# main.net
KiCad netlist of a schematic drawn in Altium Designer
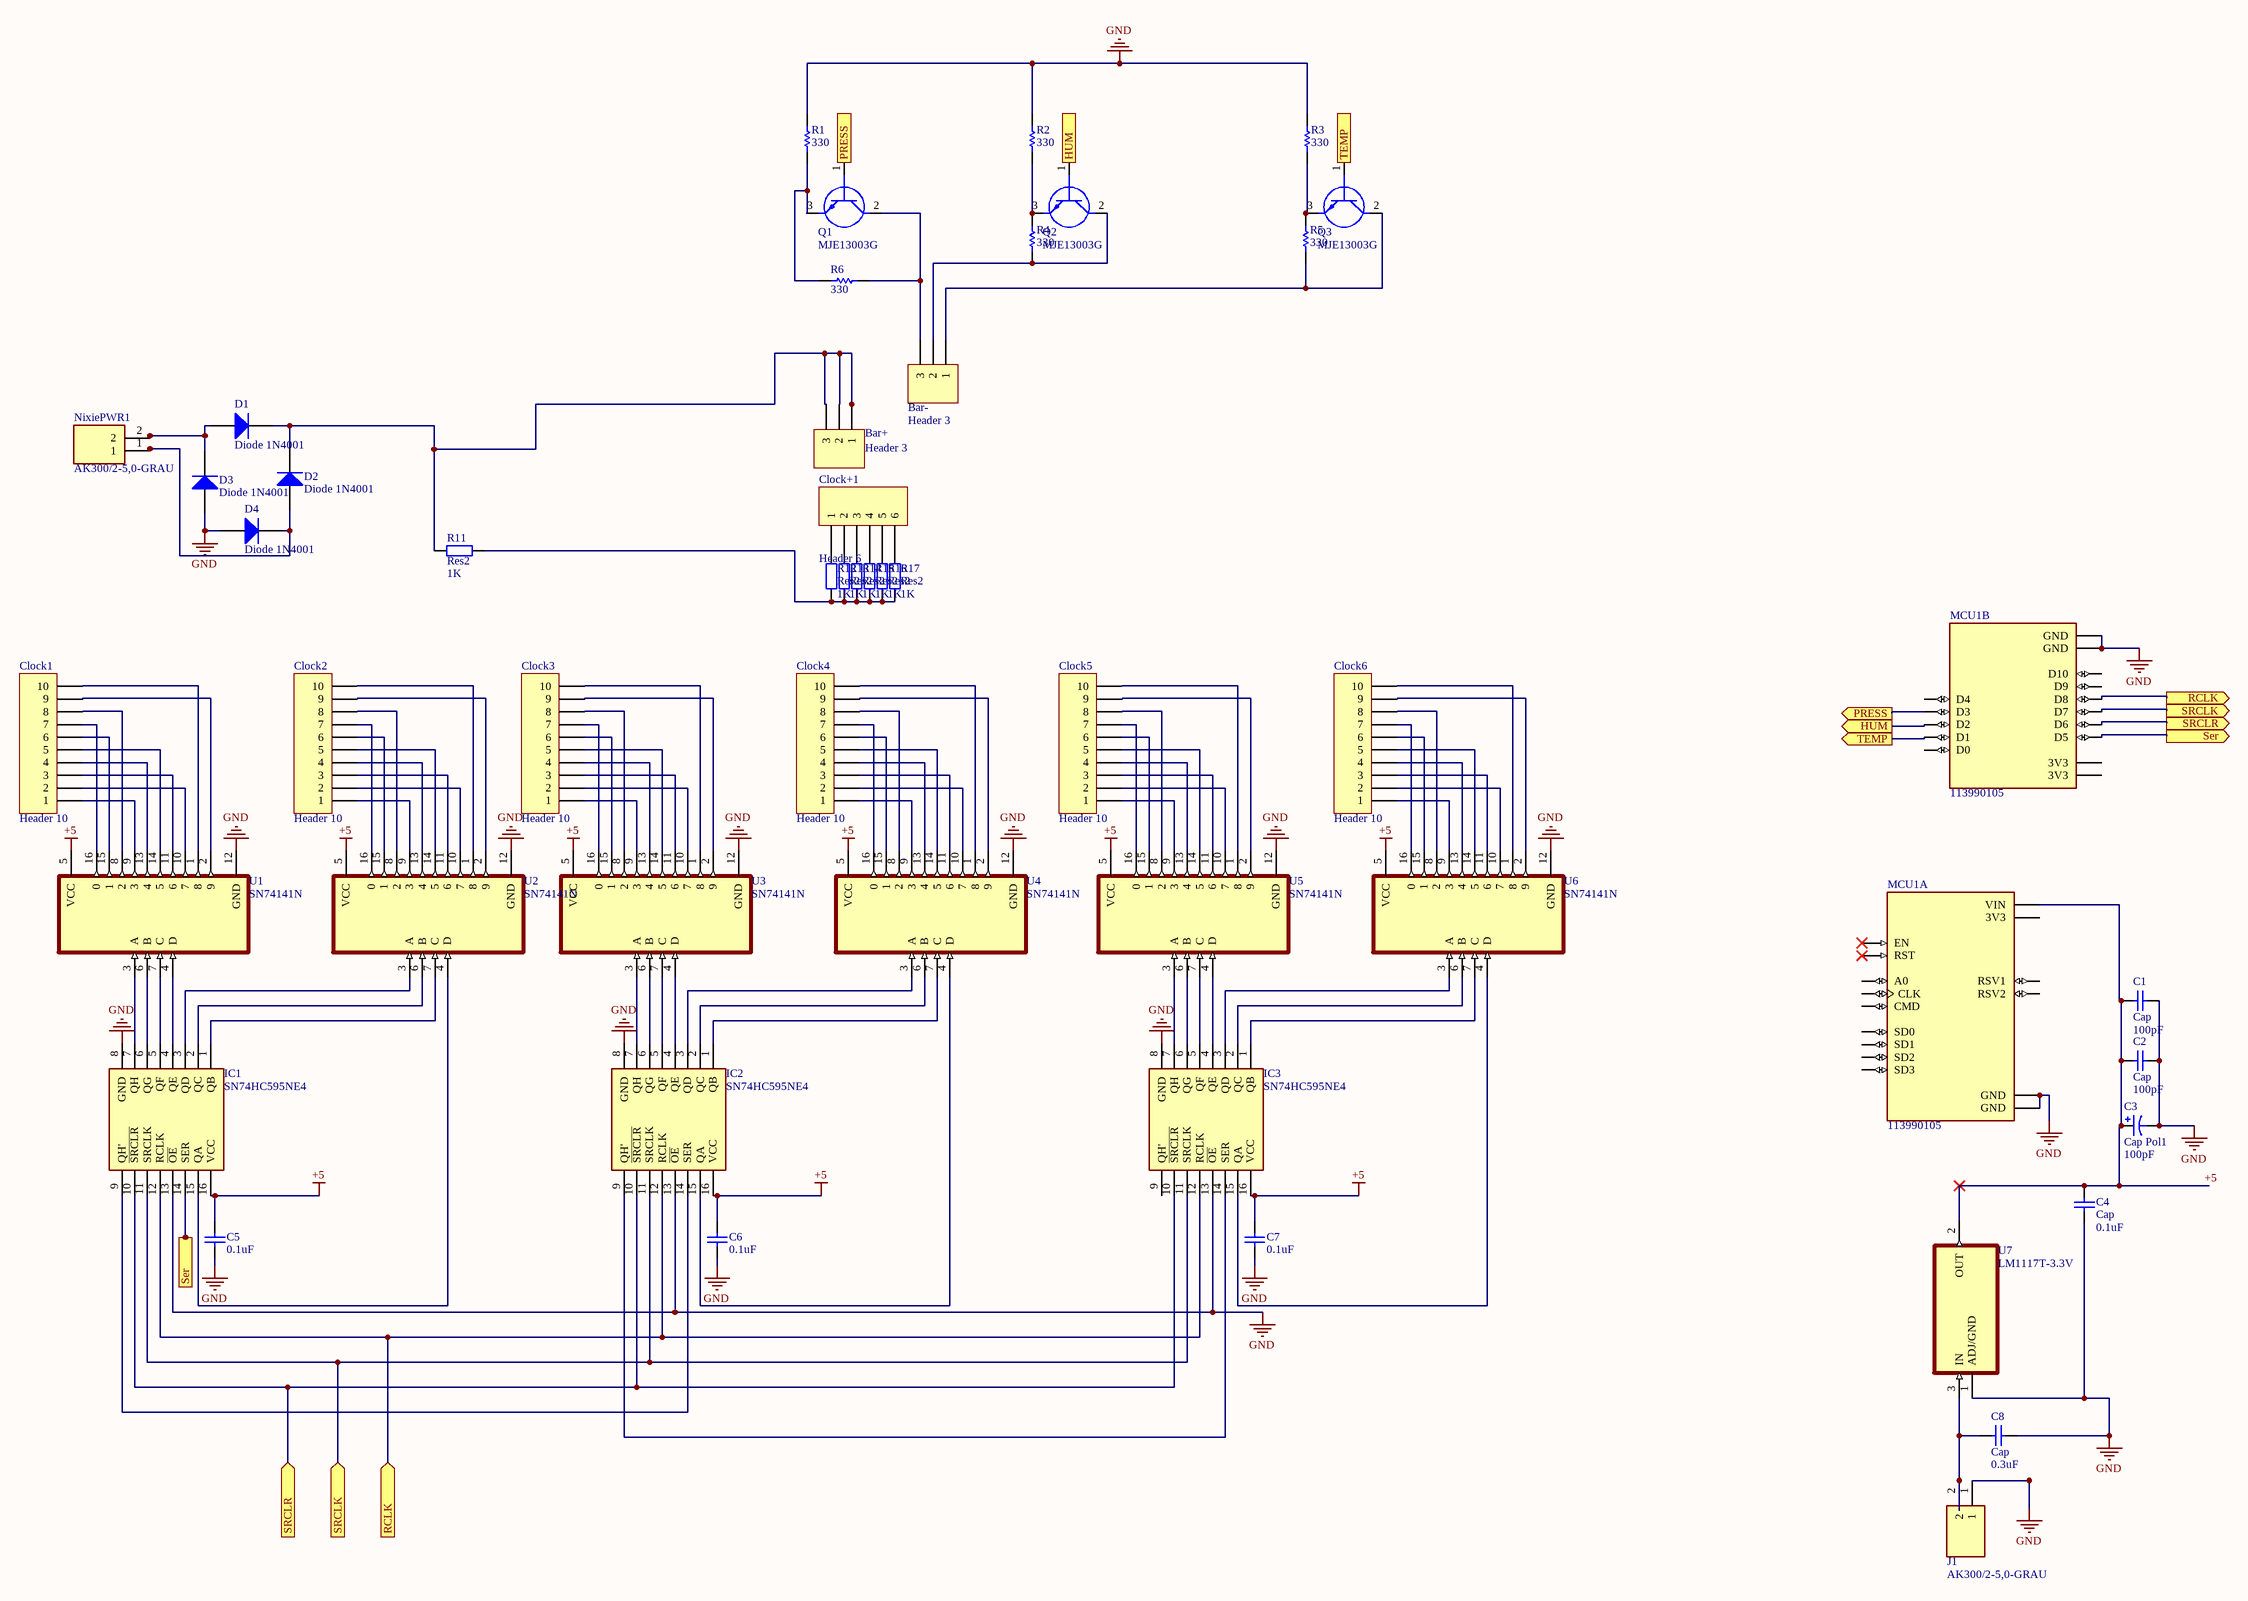
[diagram p0: main.SchDoc]

(export (version "E")
  (design (tool "Eeschema 10.0.6"))
  (components
    (comp (ref "Bar+")
      (value "Header 3")
      (footprint "HDR1X3")
      (description "Header, 3-Pin")
      (fields (field (name "PUBLISHER") "Altium Limited"))
      (libsource (lib "Miscellaneous Connectors") (part "Header 3"))
    )
    (comp (ref "Bar-")
      (value "Header 3")
      (footprint "HDR1X3")
      (description "Header, 3-Pin")
      (fields (field (name "PUBLISHER") "Altium Limited"))
      (libsource (lib "Miscellaneous Connectors") (part "Header 3"))
    )
    (comp (ref "C1")
      (value "Cap")
      (footprint "AXIAL-0.3")
      (description "Capacitor")
      (fields (field (name "ALTIUM_VALUE") "100pF") (field (name "PUBLISHER") "Altium Limited"))
      (libsource (lib "Miscellaneous Devices") (part "Cap"))
    )
    (comp (ref "C2")
      (value "Cap")
      (footprint "AXIAL-0.3")
      (description "Capacitor")
      (fields (field (name "ALTIUM_VALUE") "100pF") (field (name "PUBLISHER") "Altium Limited"))
      (libsource (lib "Miscellaneous Devices") (part "Cap"))
    )
    (comp (ref "C3")
      (value "Cap Pol1")
      (footprint "CAPR5-4X5")
      (description "Polarized Capacitor (Radial)")
      (fields (field (name "ALTIUM_VALUE") "100pF") (field (name "PUBLISHER") "Altium Limited"))
      (libsource (lib "Miscellaneous Devices") (part "Cap Pol1"))
    )
    (comp (ref "C4")
      (value "Cap")
      (footprint "AXIAL-0.3")
      (description "Capacitor")
      (fields (field (name "ALTIUM_VALUE") "0.1uF") (field (name "PUBLISHER") "Altium Limited"))
      (libsource (lib "Miscellaneous Devices") (part "Cap"))
    )
    (comp (ref "C5")
      (value "0.1uF")
      (footprint "AXIAL-0.3")
      (description "Capacitor")
      (fields (field (name "Comment") "Cap") (field (name "PUBLISHER") "Altium Limited"))
      (libsource (lib "Miscellaneous Devices") (part "Cap"))
    )
    (comp (ref "C6")
      (value "0.1uF")
      (footprint "AXIAL-0.3")
      (description "Capacitor")
      (fields (field (name "Comment") "Cap") (field (name "PUBLISHER") "Altium Limited"))
      (libsource (lib "Miscellaneous Devices") (part "Cap"))
    )
    (comp (ref "C7")
      (value "0.1uF")
      (footprint "AXIAL-0.3")
      (description "Capacitor")
      (fields (field (name "Comment") "Cap") (field (name "PUBLISHER") "Altium Limited"))
      (libsource (lib "Miscellaneous Devices") (part "Cap"))
    )
    (comp (ref "C8")
      (value "Cap")
      (footprint "AXIAL-0.3")
      (description "Capacitor")
      (fields (field (name "ALTIUM_VALUE") "0.3uF") (field (name "PUBLISHER") "Altium Limited"))
      (libsource (lib "Miscellaneous Devices") (part "Cap"))
    )
    (comp (ref "Clock+1")
      (value "Header 6")
      (footprint "HDR1X6")
      (description "Header, 6-Pin")
      (fields (field (name "PUBLISHER") "Altium Limited"))
      (libsource (lib "Miscellaneous Connectors") (part "Header 6"))
    )
    (comp (ref "Clock1")
      (value "Header 10")
      (footprint "HDR1X10")
      (description "Header, 10-Pin")
      (fields (field (name "PUBLISHER") "Altium Limited"))
      (libsource (lib "Miscellaneous Connectors") (part "Header 10"))
    )
    (comp (ref "Clock2")
      (value "Header 10")
      (footprint "HDR1X10")
      (description "Header, 10-Pin")
      (fields (field (name "PUBLISHER") "Altium Limited"))
      (libsource (lib "Miscellaneous Connectors") (part "Header 10"))
    )
    (comp (ref "Clock3")
      (value "Header 10")
      (footprint "HDR1X10")
      (description "Header, 10-Pin")
      (fields (field (name "PUBLISHER") "Altium Limited"))
      (libsource (lib "Miscellaneous Connectors") (part "Header 10"))
    )
    (comp (ref "Clock4")
      (value "Header 10")
      (footprint "HDR1X10")
      (description "Header, 10-Pin")
      (fields (field (name "PUBLISHER") "Altium Limited"))
      (libsource (lib "Miscellaneous Connectors") (part "Header 10"))
    )
    (comp (ref "Clock5")
      (value "Header 10")
      (footprint "HDR1X10")
      (description "Header, 10-Pin")
      (fields (field (name "PUBLISHER") "Altium Limited"))
      (libsource (lib "Miscellaneous Connectors") (part "Header 10"))
    )
    (comp (ref "Clock6")
      (value "Header 10")
      (footprint "HDR1X10")
      (description "Header, 10-Pin")
      (fields (field (name "PUBLISHER") "Altium Limited"))
      (libsource (lib "Miscellaneous Connectors") (part "Header 10"))
    )
    (comp (ref "D1")
      (value "Diode 1N4001")
      (footprint "DO-41")
      (description "1 Amp General Purpose Rectifier")
      (fields (field (name "PUBLISHER") "Altium Limited"))
      (libsource (lib "Miscellaneous Devices") (part "Diode 1N4001"))
    )
    (comp (ref "D2")
      (value "Diode 1N4001")
      (footprint "DO-41")
      (description "1 Amp General Purpose Rectifier")
      (fields (field (name "PUBLISHER") "Altium Limited"))
      (libsource (lib "Miscellaneous Devices") (part "Diode 1N4001"))
    )
    (comp (ref "D3")
      (value "Diode 1N4001")
      (footprint "DO-41")
      (description "1 Amp General Purpose Rectifier")
      (fields (field (name "PUBLISHER") "Altium Limited"))
      (libsource (lib "Miscellaneous Devices") (part "Diode 1N4001"))
    )
    (comp (ref "D4")
      (value "Diode 1N4001")
      (footprint "DO-41")
      (description "1 Amp General Purpose Rectifier")
      (fields (field (name "PUBLISHER") "Altium Limited"))
      (libsource (lib "Miscellaneous Devices") (part "Diode 1N4001"))
    )
    (comp (ref "IC1")
      (value "SN74HC595NE4")
      (footprint "SamacSys:DIP794W53P254L1930H508Q16N")
      (description "Integrated Circuit")
      (fields (field (name "MOUSER PART NUMBER") "595-SN74HC595NE4"))
      (libsource (lib "*") (part "SN74HC595NE4"))
    )
    (comp (ref "IC2")
      (value "SN74HC595NE4")
      (footprint "SamacSys:DIP794W53P254L1930H508Q16N")
      (description "Integrated Circuit")
      (fields (field (name "MOUSER PART NUMBER") "595-SN74HC595NE4"))
      (libsource (lib "*") (part "SN74HC595NE4"))
    )
    (comp (ref "IC3")
      (value "SN74HC595NE4")
      (footprint "SamacSys:DIP794W53P254L1930H508Q16N")
      (description "Integrated Circuit")
      (fields (field (name "MOUSER PART NUMBER") "595-SN74HC595NE4"))
      (libsource (lib "*") (part "SN74HC595NE4"))
    )
    (comp (ref "J1")
      (value "AK300/2-5,0-GRAU")
      (footprint "*PTR_AK300/2-5,0-GRAU")
      (description "Terminal block; 5mm; angled 45Â°; ways: 2")
      (fields (field (name "MF") "PTR Messtechnik"))
      (libsource (lib "") (part "AK300/2-5,0-GRAU_1"))
    )
    (comp (ref "MCU1")
      (value "113990105")
      (footprint "*SEEED_113990105_113990105(Primary)")
      (fields (field (name "MP") "NodeMCU v2") (field (name "MF") "Seeed Technology"))
      (libsource (lib "") (part "113990105_1"))
    )
    (comp (ref "NixiePWR1")
      (value "AK300/2-5,0-GRAU")
      (footprint "*PTR_AK300/2-5,0-GRAU")
      (description "Terminal block; 5mm; angled 45Â°; ways: 2")
      (fields (field (name "MF") "PTR Messtechnik"))
      (libsource (lib "AK300_2-5_0-GRAU") (part "AK300/2-5,0-GRAU"))
    )
    (comp (ref "Q1")
      (value "MJE13003G")
      (footprint "SamacSys:TO229P300X760X1364-3P")
      (description "Transistor BJT NPN")
      (fields (field (name "MOUSER PART NUMBER") "863-MJE13003G"))
      (libsource (lib "*") (part "MJE13003G"))
    )
    (comp (ref "Q2")
      (value "MJE13003G")
      (footprint "SamacSys:TO229P300X760X1364-3P")
      (description "Transistor BJT NPN")
      (fields (field (name "MOUSER PART NUMBER") "863-MJE13003G"))
      (libsource (lib "*") (part "MJE13003G"))
    )
    (comp (ref "Q3")
      (value "MJE13003G")
      (footprint "SamacSys:TO229P300X760X1364-3P")
      (description "Transistor BJT NPN")
      (fields (field (name "MOUSER PART NUMBER") "863-MJE13003G"))
      (libsource (lib "*") (part "MJE13003G"))
    )
    (comp (ref "R1")
      (value "330")
      (footprint "AXIAL-0.3")
      (description "Resistor")
      (fields (field (name "PUBLISHER") "Altium Limited"))
      (libsource (lib "Miscellaneous Devices") (part "Res1"))
    )
    (comp (ref "R2")
      (value "330")
      (footprint "AXIAL-0.3")
      (description "Resistor")
      (fields (field (name "PUBLISHER") "Altium Limited"))
      (libsource (lib "Miscellaneous Devices") (part "Res1"))
    )
    (comp (ref "R3")
      (value "330")
      (footprint "AXIAL-0.3")
      (description "Resistor")
      (fields (field (name "PUBLISHER") "Altium Limited"))
      (libsource (lib "Miscellaneous Devices") (part "Res1"))
    )
    (comp (ref "R4")
      (value "330")
      (footprint "AXIAL-0.3")
      (description "Resistor")
      (fields (field (name "PUBLISHER") "Altium Limited"))
      (libsource (lib "Miscellaneous Devices") (part "Res1"))
    )
    (comp (ref "R5")
      (value "330")
      (footprint "AXIAL-0.3")
      (description "Resistor")
      (fields (field (name "PUBLISHER") "Altium Limited"))
      (libsource (lib "Miscellaneous Devices") (part "Res1"))
    )
    (comp (ref "R6")
      (value "330")
      (footprint "AXIAL-0.3")
      (description "Resistor")
      (fields (field (name "PUBLISHER") "Altium Limited"))
      (libsource (lib "Miscellaneous Devices") (part "Res1"))
    )
    (comp (ref "R11")
      (value "Res2")
      (footprint "AXIAL-0.4")
      (description "Resistor")
      (fields (field (name "ALTIUM_VALUE") "1K") (field (name "PUBLISHER") "Altium Limited"))
      (libsource (lib "") (part "Res2_1"))
    )
    (comp (ref "R12")
      (value "Res2")
      (footprint "AXIAL-0.4")
      (description "Resistor")
      (fields (field (name "ALTIUM_VALUE") "1K") (field (name "PUBLISHER") "Altium Limited"))
      (libsource (lib "Miscellaneous Devices") (part "Res2"))
    )
    (comp (ref "R13")
      (value "Res2")
      (footprint "AXIAL-0.4")
      (description "Resistor")
      (fields (field (name "ALTIUM_VALUE") "1K") (field (name "PUBLISHER") "Altium Limited"))
      (libsource (lib "Miscellaneous Devices") (part "Res2"))
    )
    (comp (ref "R14")
      (value "Res2")
      (footprint "AXIAL-0.4")
      (description "Resistor")
      (fields (field (name "ALTIUM_VALUE") "1K") (field (name "PUBLISHER") "Altium Limited"))
      (libsource (lib "Miscellaneous Devices") (part "Res2"))
    )
    (comp (ref "R15")
      (value "Res2")
      (footprint "AXIAL-0.4")
      (description "Resistor")
      (fields (field (name "ALTIUM_VALUE") "1K") (field (name "PUBLISHER") "Altium Limited"))
      (libsource (lib "Miscellaneous Devices") (part "Res2"))
    )
    (comp (ref "R16")
      (value "Res2")
      (footprint "AXIAL-0.4")
      (description "Resistor")
      (fields (field (name "ALTIUM_VALUE") "1K") (field (name "PUBLISHER") "Altium Limited"))
      (libsource (lib "Miscellaneous Devices") (part "Res2"))
    )
    (comp (ref "R17")
      (value "Res2")
      (footprint "AXIAL-0.4")
      (description "Resistor")
      (fields (field (name "ALTIUM_VALUE") "1K") (field (name "PUBLISHER") "Altium Limited"))
      (libsource (lib "Miscellaneous Devices") (part "Res2"))
    )
    (comp (ref "U1")
      (value "SN74141N")
      (footprint "*DIP762W46P254L2134H508Q16")
      (description "BCD to DECIMAL Decoder/Driver")
      (fields (field (name "MF") "Texas Instruments"))
      (libsource (lib "SN74141N") (part "SN74141N"))
    )
    (comp (ref "U2")
      (value "SN74141N")
      (footprint "*DIP762W46P254L2134H508Q16")
      (description "BCD to DECIMAL Decoder/Driver")
      (fields (field (name "MF") "Texas Instruments"))
      (libsource (lib "SN74141N") (part "SN74141N"))
    )
    (comp (ref "U3")
      (value "SN74141N")
      (footprint "*DIP762W46P254L2134H508Q16")
      (description "BCD to DECIMAL Decoder/Driver")
      (fields (field (name "MF") "Texas Instruments"))
      (libsource (lib "SN74141N") (part "SN74141N"))
    )
    (comp (ref "U4")
      (value "SN74141N")
      (footprint "*DIP762W46P254L2134H508Q16")
      (description "BCD to DECIMAL Decoder/Driver")
      (fields (field (name "MF") "Texas Instruments"))
      (libsource (lib "SN74141N") (part "SN74141N"))
    )
    (comp (ref "U5")
      (value "SN74141N")
      (footprint "*DIP762W46P254L2134H508Q16")
      (description "BCD to DECIMAL Decoder/Driver")
      (fields (field (name "MF") "Texas Instruments"))
      (libsource (lib "SN74141N") (part "SN74141N"))
    )
    (comp (ref "U6")
      (value "SN74141N")
      (footprint "*DIP762W46P254L2134H508Q16")
      (description "BCD to DECIMAL Decoder/Driver")
      (fields (field (name "MF") "Texas Instruments"))
      (libsource (lib "SN74141N") (part "SN74141N"))
    )
    (comp (ref "U7")
      (value "LM1117T-3.3V")
      (footprint "*TO254P470X1016X2222-3P")
      (description "Linear Voltage Regulator IC 1 Output 800mA TO-220-3")
      (fields (field (name "MF") "Texas Instruments") (field (name "MP") "LM1117T50"))
      (libsource (lib "LM1117T-5.0") (part "LM1117T-5.0"))
    )
  )
  (nets
    (net (code "1") (name "+5") (class "Default")
      (node (ref "C1") (pin "1") (pinfunction "1_1") (pintype "passive"))
      (node (ref "C2") (pin "1") (pinfunction "1_1") (pintype "passive"))
      (node (ref "C3") (pin "1") (pinfunction "1_1") (pintype "passive"))
      (node (ref "C4") (pin "2") (pinfunction "2_2") (pintype "passive"))
      (node (ref "C5") (pin "2") (pinfunction "2_2") (pintype "passive"))
      (node (ref "C6") (pin "2") (pinfunction "2_2") (pintype "passive"))
      (node (ref "C7") (pin "2") (pinfunction "2_2") (pintype "passive"))
      (node (ref "IC1") (pin "16") (pinfunction "VCC_16") (pintype "passive"))
      (node (ref "IC2") (pin "16") (pinfunction "VCC_16") (pintype "passive"))
      (node (ref "IC3") (pin "16") (pinfunction "VCC_16") (pintype "passive"))
      (node (ref "MCU1") (pin "J1_15") (pinfunction "VIN_J1_15") (pintype "power_in"))
      (node (ref "U1") (pin "5") (pinfunction "VCC_5") (pintype "power_in"))
      (node (ref "U2") (pin "5") (pinfunction "VCC_5") (pintype "power_in"))
      (node (ref "U3") (pin "5") (pinfunction "VCC_5") (pintype "power_in"))
      (node (ref "U4") (pin "5") (pinfunction "VCC_5") (pintype "power_in"))
      (node (ref "U5") (pin "5") (pinfunction "VCC_5") (pintype "power_in"))
      (node (ref "U6") (pin "5") (pinfunction "VCC_5") (pintype "power_in"))
      (node (ref "U7") (pin "2") (pinfunction "OUT_2") (pintype "output"))
    )
    (net (code "2") (name "/HUM") (class "Default")
      (node (ref "MCU1") (pin "J2_3") (pinfunction "D2_J2_3") (pintype "bidirectional"))
      (node (ref "Q2") (pin "1") (pinfunction "B_1") (pintype "passive"))
    )
    (net (code "3") (name "/PRESS") (class "Default")
      (node (ref "MCU1") (pin "J2_4") (pinfunction "D3_J2_4") (pintype "bidirectional"))
      (node (ref "Q1") (pin "1") (pinfunction "B_1") (pintype "passive"))
    )
    (net (code "4") (name "/RCLK") (class "Default")
      (node (ref "IC1") (pin "12") (pinfunction "RCLK_12") (pintype "passive"))
      (node (ref "IC2") (pin "12") (pinfunction "RCLK_12") (pintype "passive"))
      (node (ref "IC3") (pin "12") (pinfunction "RCLK_12") (pintype "passive"))
      (node (ref "MCU1") (pin "J2_11") (pinfunction "D8_J2_11") (pintype "bidirectional"))
    )
    (net (code "5") (name "/SRCLK") (class "Default")
      (node (ref "IC1") (pin "11") (pinfunction "SRCLK_11") (pintype "passive"))
      (node (ref "IC2") (pin "11") (pinfunction "SRCLK_11") (pintype "passive"))
      (node (ref "IC3") (pin "11") (pinfunction "SRCLK_11") (pintype "passive"))
      (node (ref "MCU1") (pin "J2_10") (pinfunction "D7_J2_10") (pintype "bidirectional"))
    )
    (net (code "6") (name "/SRCLR") (class "Default")
      (node (ref "IC1") (pin "10") (pinfunction "~{SRCLR}_10") (pintype "passive"))
      (node (ref "IC2") (pin "10") (pinfunction "~{SRCLR}_10") (pintype "passive"))
      (node (ref "IC3") (pin "10") (pinfunction "~{SRCLR}_10") (pintype "passive"))
      (node (ref "MCU1") (pin "J2_9") (pinfunction "D6_J2_9") (pintype "bidirectional"))
    )
    (net (code "7") (name "/Ser") (class "Default")
      (node (ref "IC1") (pin "14") (pinfunction "SER_14") (pintype "passive"))
      (node (ref "MCU1") (pin "J2_8") (pinfunction "D5_J2_8") (pintype "bidirectional"))
    )
    (net (code "8") (name "/TEMP") (class "Default")
      (node (ref "MCU1") (pin "J2_2") (pinfunction "D1_J2_2") (pintype "bidirectional"))
      (node (ref "Q3") (pin "1") (pinfunction "B_1") (pintype "passive"))
    )
    (net (code "9") (name "GND") (class "Default")
      (node (ref "C1") (pin "2") (pinfunction "2_2") (pintype "passive"))
      (node (ref "C2") (pin "2") (pinfunction "2_2") (pintype "passive"))
      (node (ref "C3") (pin "2") (pinfunction "2_2") (pintype "passive"))
      (node (ref "C4") (pin "1") (pinfunction "1_1") (pintype "passive"))
      (node (ref "C5") (pin "1") (pinfunction "1_1") (pintype "passive"))
      (node (ref "C6") (pin "1") (pinfunction "1_1") (pintype "passive"))
      (node (ref "C7") (pin "1") (pinfunction "1_1") (pintype "passive"))
      (node (ref "C8") (pin "1") (pinfunction "1_1") (pintype "passive"))
      (node (ref "D3") (pin "1") (pinfunction "A_1") (pintype "passive"))
      (node (ref "D4") (pin "1") (pinfunction "A_1") (pintype "passive"))
      (node (ref "IC1") (pin "13") (pinfunction "~{OE}_13") (pintype "passive"))
      (node (ref "IC1") (pin "8") (pinfunction "GND_8") (pintype "passive"))
      (node (ref "IC2") (pin "13") (pinfunction "~{OE}_13") (pintype "passive"))
      (node (ref "IC2") (pin "8") (pinfunction "GND_8") (pintype "passive"))
      (node (ref "IC3") (pin "13") (pinfunction "~{OE}_13") (pintype "passive"))
      (node (ref "IC3") (pin "8") (pinfunction "GND_8") (pintype "passive"))
      (node (ref "J1") (pin "1") (pinfunction "1_1") (pintype "passive"))
      (node (ref "MCU1") (pin "J1_10") (pinfunction "GND_J1_10") (pintype "power_in"))
      (node (ref "MCU1") (pin "J1_14") (pinfunction "GND_J1_14") (pintype "power_in"))
      (node (ref "MCU1") (pin "J2_14") (pinfunction "GND_J2_14") (pintype "power_in"))
      (node (ref "MCU1") (pin "J2_7") (pinfunction "GND_J2_7") (pintype "power_in"))
      (node (ref "R1") (pin "2") (pinfunction "2_2") (pintype "passive"))
      (node (ref "R2") (pin "2") (pinfunction "2_2") (pintype "passive"))
      (node (ref "R3") (pin "2") (pinfunction "2_2") (pintype "passive"))
      (node (ref "U1") (pin "12") (pinfunction "GND_12") (pintype "passive"))
      (node (ref "U2") (pin "12") (pinfunction "GND_12") (pintype "passive"))
      (node (ref "U3") (pin "12") (pinfunction "GND_12") (pintype "passive"))
      (node (ref "U4") (pin "12") (pinfunction "GND_12") (pintype "passive"))
      (node (ref "U5") (pin "12") (pinfunction "GND_12") (pintype "passive"))
      (node (ref "U6") (pin "12") (pinfunction "GND_12") (pintype "passive"))
      (node (ref "U7") (pin "1") (pinfunction "ADJ/GND_1") (pintype "passive"))
    )
    (net (code "10") (name "Net-(Clock+1-Pad1)") (class "Default")
      (node (ref "Clock+1") (pin "1") (pinfunction "1_1") (pintype "passive"))
      (node (ref "R12") (pin "2") (pinfunction "2_2") (pintype "passive"))
    )
    (net (code "11") (name "Net-(Clock+1-Pad2)") (class "Default")
      (node (ref "Clock+1") (pin "2") (pinfunction "2_2") (pintype "passive"))
      (node (ref "R13") (pin "2") (pinfunction "2_2") (pintype "passive"))
    )
    (net (code "12") (name "Net-(Clock+1-Pad3)") (class "Default")
      (node (ref "Clock+1") (pin "3") (pinfunction "3_3") (pintype "passive"))
      (node (ref "R14") (pin "2") (pinfunction "2_2") (pintype "passive"))
    )
    (net (code "13") (name "Net-(Clock+1-Pad4)") (class "Default")
      (node (ref "Clock+1") (pin "4") (pinfunction "4_4") (pintype "passive"))
      (node (ref "R15") (pin "2") (pinfunction "2_2") (pintype "passive"))
    )
    (net (code "14") (name "Net-(Clock+1-Pad5)") (class "Default")
      (node (ref "Clock+1") (pin "5") (pinfunction "5_5") (pintype "passive"))
      (node (ref "R16") (pin "2") (pinfunction "2_2") (pintype "passive"))
    )
    (net (code "15") (name "Net-(Clock+1-Pad6)") (class "Default")
      (node (ref "Clock+1") (pin "6") (pinfunction "6_6") (pintype "passive"))
      (node (ref "R17") (pin "2") (pinfunction "2_2") (pintype "passive"))
    )
    (net (code "16") (name "Net-(D1-A)") (class "Default")
      (node (ref "D1") (pin "1") (pinfunction "A_1") (pintype "passive"))
      (node (ref "D3") (pin "2") (pinfunction "K_2") (pintype "passive"))
      (node (ref "NixiePWR1") (pin "2") (pinfunction "2_2") (pintype "passive"))
    )
    (net (code "17") (name "Net-(D1-K)") (class "Default")
      (node (ref "Bar+") (pin "1") (pinfunction "1_1") (pintype "passive"))
      (node (ref "Bar+") (pin "2") (pinfunction "2_2") (pintype "passive"))
      (node (ref "Bar+") (pin "3") (pinfunction "3_3") (pintype "passive"))
      (node (ref "D1") (pin "2") (pinfunction "K_2") (pintype "passive"))
      (node (ref "D2") (pin "2") (pinfunction "K_2") (pintype "passive"))
      (node (ref "R11") (pin "1") (pinfunction "1_1") (pintype "passive"))
    )
    (net (code "18") (name "Net-(D2-A)") (class "Default")
      (node (ref "D2") (pin "1") (pinfunction "A_1") (pintype "passive"))
      (node (ref "D4") (pin "2") (pinfunction "K_2") (pintype "passive"))
      (node (ref "NixiePWR1") (pin "1") (pinfunction "1_1") (pintype "passive"))
    )
    (net (code "19") (name "Net-(IC1-QA)") (class "Default")
      (node (ref "IC1") (pin "15") (pinfunction "QA_15") (pintype "passive"))
      (node (ref "U2") (pin "4") (pinfunction "D_4") (pintype "input"))
    )
    (net (code "20") (name "Net-(IC1-QB)") (class "Default")
      (node (ref "IC1") (pin "1") (pinfunction "QB_1") (pintype "passive"))
      (node (ref "U2") (pin "7") (pinfunction "C_7") (pintype "input"))
    )
    (net (code "21") (name "Net-(IC1-QC)") (class "Default")
      (node (ref "IC1") (pin "2") (pinfunction "QC_2") (pintype "passive"))
      (node (ref "U2") (pin "6") (pinfunction "B_6") (pintype "input"))
    )
    (net (code "22") (name "Net-(IC1-QD)") (class "Default")
      (node (ref "IC1") (pin "3") (pinfunction "QD_3") (pintype "passive"))
      (node (ref "U2") (pin "3") (pinfunction "A_3") (pintype "input"))
    )
    (net (code "23") (name "Net-(IC1-QE)") (class "Default")
      (node (ref "IC1") (pin "4") (pinfunction "QE_4") (pintype "passive"))
      (node (ref "U1") (pin "4") (pinfunction "D_4") (pintype "input"))
    )
    (net (code "24") (name "Net-(IC1-QF)") (class "Default")
      (node (ref "IC1") (pin "5") (pinfunction "QF_5") (pintype "passive"))
      (node (ref "U1") (pin "7") (pinfunction "C_7") (pintype "input"))
    )
    (net (code "25") (name "Net-(IC1-QG)") (class "Default")
      (node (ref "IC1") (pin "6") (pinfunction "QG_6") (pintype "passive"))
      (node (ref "U1") (pin "6") (pinfunction "B_6") (pintype "input"))
    )
    (net (code "26") (name "Net-(IC1-QH')") (class "Default")
      (node (ref "IC1") (pin "9") (pinfunction "QH'_9") (pintype "passive"))
      (node (ref "IC2") (pin "14") (pinfunction "SER_14") (pintype "passive"))
    )
    (net (code "27") (name "Net-(IC1-QH)") (class "Default")
      (node (ref "IC1") (pin "7") (pinfunction "QH_7") (pintype "passive"))
      (node (ref "U1") (pin "3") (pinfunction "A_3") (pintype "input"))
    )
    (net (code "28") (name "Net-(IC2-QA)") (class "Default")
      (node (ref "IC2") (pin "15") (pinfunction "QA_15") (pintype "passive"))
      (node (ref "U4") (pin "4") (pinfunction "D_4") (pintype "input"))
    )
    (net (code "29") (name "Net-(IC2-QB)") (class "Default")
      (node (ref "IC2") (pin "1") (pinfunction "QB_1") (pintype "passive"))
      (node (ref "U4") (pin "7") (pinfunction "C_7") (pintype "input"))
    )
    (net (code "30") (name "Net-(IC2-QC)") (class "Default")
      (node (ref "IC2") (pin "2") (pinfunction "QC_2") (pintype "passive"))
      (node (ref "U4") (pin "6") (pinfunction "B_6") (pintype "input"))
    )
    (net (code "31") (name "Net-(IC2-QD)") (class "Default")
      (node (ref "IC2") (pin "3") (pinfunction "QD_3") (pintype "passive"))
      (node (ref "U4") (pin "3") (pinfunction "A_3") (pintype "input"))
    )
    (net (code "32") (name "Net-(IC2-QE)") (class "Default")
      (node (ref "IC2") (pin "4") (pinfunction "QE_4") (pintype "passive"))
      (node (ref "U3") (pin "4") (pinfunction "D_4") (pintype "input"))
    )
    (net (code "33") (name "Net-(IC2-QF)") (class "Default")
      (node (ref "IC2") (pin "5") (pinfunction "QF_5") (pintype "passive"))
      (node (ref "U3") (pin "7") (pinfunction "C_7") (pintype "input"))
    )
    (net (code "34") (name "Net-(IC2-QG)") (class "Default")
      (node (ref "IC2") (pin "6") (pinfunction "QG_6") (pintype "passive"))
      (node (ref "U3") (pin "6") (pinfunction "B_6") (pintype "input"))
    )
    (net (code "35") (name "Net-(IC2-QH')") (class "Default")
      (node (ref "IC2") (pin "9") (pinfunction "QH'_9") (pintype "passive"))
      (node (ref "IC3") (pin "14") (pinfunction "SER_14") (pintype "passive"))
    )
    (net (code "36") (name "Net-(IC2-QH)") (class "Default")
      (node (ref "IC2") (pin "7") (pinfunction "QH_7") (pintype "passive"))
      (node (ref "U3") (pin "3") (pinfunction "A_3") (pintype "input"))
    )
    (net (code "37") (name "Net-(IC3-QA)") (class "Default")
      (node (ref "IC3") (pin "15") (pinfunction "QA_15") (pintype "passive"))
      (node (ref "U6") (pin "4") (pinfunction "D_4") (pintype "input"))
    )
    (net (code "38") (name "Net-(IC3-QB)") (class "Default")
      (node (ref "IC3") (pin "1") (pinfunction "QB_1") (pintype "passive"))
      (node (ref "U6") (pin "7") (pinfunction "C_7") (pintype "input"))
    )
    (net (code "39") (name "Net-(IC3-QC)") (class "Default")
      (node (ref "IC3") (pin "2") (pinfunction "QC_2") (pintype "passive"))
      (node (ref "U6") (pin "6") (pinfunction "B_6") (pintype "input"))
    )
    (net (code "40") (name "Net-(IC3-QD)") (class "Default")
      (node (ref "IC3") (pin "3") (pinfunction "QD_3") (pintype "passive"))
      (node (ref "U6") (pin "3") (pinfunction "A_3") (pintype "input"))
    )
    (net (code "41") (name "Net-(IC3-QE)") (class "Default")
      (node (ref "IC3") (pin "4") (pinfunction "QE_4") (pintype "passive"))
      (node (ref "U5") (pin "4") (pinfunction "D_4") (pintype "input"))
    )
    (net (code "42") (name "Net-(IC3-QF)") (class "Default")
      (node (ref "IC3") (pin "5") (pinfunction "QF_5") (pintype "passive"))
      (node (ref "U5") (pin "7") (pinfunction "C_7") (pintype "input"))
    )
    (net (code "43") (name "Net-(IC3-QG)") (class "Default")
      (node (ref "IC3") (pin "6") (pinfunction "QG_6") (pintype "passive"))
      (node (ref "U5") (pin "6") (pinfunction "B_6") (pintype "input"))
    )
    (net (code "44") (name "Net-(IC3-QH)") (class "Default")
      (node (ref "IC3") (pin "7") (pinfunction "QH_7") (pintype "passive"))
      (node (ref "U5") (pin "3") (pinfunction "A_3") (pintype "input"))
    )
    (net (code "45") (name "Net-(Q1-C)") (class "Default")
      (node (ref "Bar-") (pin "3") (pinfunction "3_3") (pintype "passive"))
      (node (ref "Q1") (pin "2") (pinfunction "C_2") (pintype "passive"))
      (node (ref "R6") (pin "1") (pinfunction "1_1") (pintype "passive"))
    )
    (net (code "46") (name "Net-(Q1-E)") (class "Default")
      (node (ref "Q1") (pin "3") (pinfunction "E_3") (pintype "passive"))
      (node (ref "R1") (pin "1") (pinfunction "1_1") (pintype "passive"))
      (node (ref "R6") (pin "2") (pinfunction "2_2") (pintype "passive"))
    )
    (net (code "47") (name "Net-(Q2-C)") (class "Default")
      (node (ref "Bar-") (pin "2") (pinfunction "2_2") (pintype "passive"))
      (node (ref "Q2") (pin "2") (pinfunction "C_2") (pintype "passive"))
      (node (ref "R4") (pin "1") (pinfunction "1_1") (pintype "passive"))
    )
    (net (code "48") (name "Net-(Q2-E)") (class "Default")
      (node (ref "Q2") (pin "3") (pinfunction "E_3") (pintype "passive"))
      (node (ref "R2") (pin "1") (pinfunction "1_1") (pintype "passive"))
      (node (ref "R4") (pin "2") (pinfunction "2_2") (pintype "passive"))
    )
    (net (code "49") (name "Net-(Q3-C)") (class "Default")
      (node (ref "Bar-") (pin "1") (pinfunction "1_1") (pintype "passive"))
      (node (ref "Q3") (pin "2") (pinfunction "C_2") (pintype "passive"))
      (node (ref "R5") (pin "1") (pinfunction "1_1") (pintype "passive"))
    )
    (net (code "50") (name "Net-(Q3-E)") (class "Default")
      (node (ref "Q3") (pin "3") (pinfunction "E_3") (pintype "passive"))
      (node (ref "R3") (pin "1") (pinfunction "1_1") (pintype "passive"))
      (node (ref "R5") (pin "2") (pinfunction "2_2") (pintype "passive"))
    )
    (net (code "51") (name "Net-(R11-Pad2)") (class "Default")
      (node (ref "R11") (pin "2") (pinfunction "2_2") (pintype "passive"))
      (node (ref "R12") (pin "1") (pinfunction "1_1") (pintype "passive"))
      (node (ref "R13") (pin "1") (pinfunction "1_1") (pintype "passive"))
      (node (ref "R14") (pin "1") (pinfunction "1_1") (pintype "passive"))
      (node (ref "R15") (pin "1") (pinfunction "1_1") (pintype "passive"))
      (node (ref "R16") (pin "1") (pinfunction "1_1") (pintype "passive"))
      (node (ref "R17") (pin "1") (pinfunction "1_1") (pintype "passive"))
    )
    (net (code "52") (name "Net-(U1-0)") (class "Default")
      (node (ref "Clock1") (pin "7") (pinfunction "7_7") (pintype "passive"))
      (node (ref "U1") (pin "16") (pinfunction "0_16") (pintype "output"))
    )
    (net (code "53") (name "Net-(U1-1)") (class "Default")
      (node (ref "Clock1") (pin "6") (pinfunction "6_6") (pintype "passive"))
      (node (ref "U1") (pin "15") (pinfunction "1_15") (pintype "output"))
    )
    (net (code "54") (name "Net-(U1-2)") (class "Default")
      (node (ref "Clock1") (pin "8") (pinfunction "8_8") (pintype "passive"))
      (node (ref "U1") (pin "8") (pinfunction "2_8") (pintype "output"))
    )
    (net (code "55") (name "Net-(U1-3)") (class "Default")
      (node (ref "Clock1") (pin "1") (pinfunction "1_1") (pintype "passive"))
      (node (ref "U1") (pin "9") (pinfunction "3_9") (pintype "output"))
    )
    (net (code "56") (name "Net-(U1-4)") (class "Default")
      (node (ref "Clock1") (pin "4") (pinfunction "4_4") (pintype "passive"))
      (node (ref "U1") (pin "13") (pinfunction "4_13") (pintype "output"))
    )
    (net (code "57") (name "Net-(U1-5)") (class "Default")
      (node (ref "Clock1") (pin "5") (pinfunction "5_5") (pintype "passive"))
      (node (ref "U1") (pin "14") (pinfunction "5_14") (pintype "output"))
    )
    (net (code "58") (name "Net-(U1-6)") (class "Default")
      (node (ref "Clock1") (pin "3") (pinfunction "3_3") (pintype "passive"))
      (node (ref "U1") (pin "11") (pinfunction "6_11") (pintype "output"))
    )
    (net (code "59") (name "Net-(U1-7)") (class "Default")
      (node (ref "Clock1") (pin "2") (pinfunction "2_2") (pintype "passive"))
      (node (ref "U1") (pin "10") (pinfunction "7_10") (pintype "output"))
    )
    (net (code "60") (name "Net-(U1-8)") (class "Default")
      (node (ref "Clock1") (pin "10") (pinfunction "10_10") (pintype "passive"))
      (node (ref "U1") (pin "1") (pinfunction "8_1") (pintype "output"))
    )
    (net (code "61") (name "Net-(U1-9)") (class "Default")
      (node (ref "Clock1") (pin "9") (pinfunction "9_9") (pintype "passive"))
      (node (ref "U1") (pin "2") (pinfunction "9_2") (pintype "output"))
    )
    (net (code "62") (name "Net-(U2-0)") (class "Default")
      (node (ref "Clock2") (pin "7") (pinfunction "7_7") (pintype "passive"))
      (node (ref "U2") (pin "16") (pinfunction "0_16") (pintype "output"))
    )
    (net (code "63") (name "Net-(U2-1)") (class "Default")
      (node (ref "Clock2") (pin "6") (pinfunction "6_6") (pintype "passive"))
      (node (ref "U2") (pin "15") (pinfunction "1_15") (pintype "output"))
    )
    (net (code "64") (name "Net-(U2-2)") (class "Default")
      (node (ref "Clock2") (pin "8") (pinfunction "8_8") (pintype "passive"))
      (node (ref "U2") (pin "8") (pinfunction "2_8") (pintype "output"))
    )
    (net (code "65") (name "Net-(U2-3)") (class "Default")
      (node (ref "Clock2") (pin "1") (pinfunction "1_1") (pintype "passive"))
      (node (ref "U2") (pin "9") (pinfunction "3_9") (pintype "output"))
    )
    (net (code "66") (name "Net-(U2-4)") (class "Default")
      (node (ref "Clock2") (pin "4") (pinfunction "4_4") (pintype "passive"))
      (node (ref "U2") (pin "13") (pinfunction "4_13") (pintype "output"))
    )
    (net (code "67") (name "Net-(U2-5)") (class "Default")
      (node (ref "Clock2") (pin "5") (pinfunction "5_5") (pintype "passive"))
      (node (ref "U2") (pin "14") (pinfunction "5_14") (pintype "output"))
    )
    (net (code "68") (name "Net-(U2-6)") (class "Default")
      (node (ref "Clock2") (pin "3") (pinfunction "3_3") (pintype "passive"))
      (node (ref "U2") (pin "11") (pinfunction "6_11") (pintype "output"))
    )
    (net (code "69") (name "Net-(U2-7)") (class "Default")
      (node (ref "Clock2") (pin "2") (pinfunction "2_2") (pintype "passive"))
      (node (ref "U2") (pin "10") (pinfunction "7_10") (pintype "output"))
    )
    (net (code "70") (name "Net-(U2-8)") (class "Default")
      (node (ref "Clock2") (pin "10") (pinfunction "10_10") (pintype "passive"))
      (node (ref "U2") (pin "1") (pinfunction "8_1") (pintype "output"))
    )
    (net (code "71") (name "Net-(U2-9)") (class "Default")
      (node (ref "Clock2") (pin "9") (pinfunction "9_9") (pintype "passive"))
      (node (ref "U2") (pin "2") (pinfunction "9_2") (pintype "output"))
    )
    (net (code "72") (name "Net-(U3-0)") (class "Default")
      (node (ref "Clock3") (pin "7") (pinfunction "7_7") (pintype "passive"))
      (node (ref "U3") (pin "16") (pinfunction "0_16") (pintype "output"))
    )
    (net (code "73") (name "Net-(U3-1)") (class "Default")
      (node (ref "Clock3") (pin "6") (pinfunction "6_6") (pintype "passive"))
      (node (ref "U3") (pin "15") (pinfunction "1_15") (pintype "output"))
    )
    (net (code "74") (name "Net-(U3-2)") (class "Default")
      (node (ref "Clock3") (pin "8") (pinfunction "8_8") (pintype "passive"))
      (node (ref "U3") (pin "8") (pinfunction "2_8") (pintype "output"))
    )
    (net (code "75") (name "Net-(U3-3)") (class "Default")
      (node (ref "Clock3") (pin "1") (pinfunction "1_1") (pintype "passive"))
      (node (ref "U3") (pin "9") (pinfunction "3_9") (pintype "output"))
    )
    (net (code "76") (name "Net-(U3-4)") (class "Default")
      (node (ref "Clock3") (pin "4") (pinfunction "4_4") (pintype "passive"))
      (node (ref "U3") (pin "13") (pinfunction "4_13") (pintype "output"))
    )
    (net (code "77") (name "Net-(U3-5)") (class "Default")
      (node (ref "Clock3") (pin "5") (pinfunction "5_5") (pintype "passive"))
      (node (ref "U3") (pin "14") (pinfunction "5_14") (pintype "output"))
    )
    (net (code "78") (name "Net-(U3-6)") (class "Default")
      (node (ref "Clock3") (pin "3") (pinfunction "3_3") (pintype "passive"))
      (node (ref "U3") (pin "11") (pinfunction "6_11") (pintype "output"))
    )
    (net (code "79") (name "Net-(U3-7)") (class "Default")
      (node (ref "Clock3") (pin "2") (pinfunction "2_2") (pintype "passive"))
      (node (ref "U3") (pin "10") (pinfunction "7_10") (pintype "output"))
    )
    (net (code "80") (name "Net-(U3-8)") (class "Default")
      (node (ref "Clock3") (pin "10") (pinfunction "10_10") (pintype "passive"))
      (node (ref "U3") (pin "1") (pinfunction "8_1") (pintype "output"))
    )
    (net (code "81") (name "Net-(U3-9)") (class "Default")
      (node (ref "Clock3") (pin "9") (pinfunction "9_9") (pintype "passive"))
      (node (ref "U3") (pin "2") (pinfunction "9_2") (pintype "output"))
    )
    (net (code "82") (name "Net-(U4-0)") (class "Default")
      (node (ref "Clock4") (pin "7") (pinfunction "7_7") (pintype "passive"))
      (node (ref "U4") (pin "16") (pinfunction "0_16") (pintype "output"))
    )
    (net (code "83") (name "Net-(U4-1)") (class "Default")
      (node (ref "Clock4") (pin "6") (pinfunction "6_6") (pintype "passive"))
      (node (ref "U4") (pin "15") (pinfunction "1_15") (pintype "output"))
    )
    (net (code "84") (name "Net-(U4-2)") (class "Default")
      (node (ref "Clock4") (pin "8") (pinfunction "8_8") (pintype "passive"))
      (node (ref "U4") (pin "8") (pinfunction "2_8") (pintype "output"))
    )
    (net (code "85") (name "Net-(U4-3)") (class "Default")
      (node (ref "Clock4") (pin "1") (pinfunction "1_1") (pintype "passive"))
      (node (ref "U4") (pin "9") (pinfunction "3_9") (pintype "output"))
    )
    (net (code "86") (name "Net-(U4-4)") (class "Default")
      (node (ref "Clock4") (pin "4") (pinfunction "4_4") (pintype "passive"))
      (node (ref "U4") (pin "13") (pinfunction "4_13") (pintype "output"))
    )
    (net (code "87") (name "Net-(U4-5)") (class "Default")
      (node (ref "Clock4") (pin "5") (pinfunction "5_5") (pintype "passive"))
      (node (ref "U4") (pin "14") (pinfunction "5_14") (pintype "output"))
    )
    (net (code "88") (name "Net-(U4-6)") (class "Default")
      (node (ref "Clock4") (pin "3") (pinfunction "3_3") (pintype "passive"))
      (node (ref "U4") (pin "11") (pinfunction "6_11") (pintype "output"))
    )
    (net (code "89") (name "Net-(U4-7)") (class "Default")
      (node (ref "Clock4") (pin "2") (pinfunction "2_2") (pintype "passive"))
      (node (ref "U4") (pin "10") (pinfunction "7_10") (pintype "output"))
    )
    (net (code "90") (name "Net-(U4-8)") (class "Default")
      (node (ref "Clock4") (pin "10") (pinfunction "10_10") (pintype "passive"))
      (node (ref "U4") (pin "1") (pinfunction "8_1") (pintype "output"))
    )
    (net (code "91") (name "Net-(U4-9)") (class "Default")
      (node (ref "Clock4") (pin "9") (pinfunction "9_9") (pintype "passive"))
      (node (ref "U4") (pin "2") (pinfunction "9_2") (pintype "output"))
    )
    (net (code "92") (name "Net-(U5-0)") (class "Default")
      (node (ref "Clock5") (pin "7") (pinfunction "7_7") (pintype "passive"))
      (node (ref "U5") (pin "16") (pinfunction "0_16") (pintype "output"))
    )
    (net (code "93") (name "Net-(U5-1)") (class "Default")
      (node (ref "Clock5") (pin "6") (pinfunction "6_6") (pintype "passive"))
      (node (ref "U5") (pin "15") (pinfunction "1_15") (pintype "output"))
    )
    (net (code "94") (name "Net-(U5-2)") (class "Default")
      (node (ref "Clock5") (pin "8") (pinfunction "8_8") (pintype "passive"))
      (node (ref "U5") (pin "8") (pinfunction "2_8") (pintype "output"))
    )
    (net (code "95") (name "Net-(U5-3)") (class "Default")
      (node (ref "Clock5") (pin "1") (pinfunction "1_1") (pintype "passive"))
      (node (ref "U5") (pin "9") (pinfunction "3_9") (pintype "output"))
    )
    (net (code "96") (name "Net-(U5-4)") (class "Default")
      (node (ref "Clock5") (pin "4") (pinfunction "4_4") (pintype "passive"))
      (node (ref "U5") (pin "13") (pinfunction "4_13") (pintype "output"))
    )
    (net (code "97") (name "Net-(U5-5)") (class "Default")
      (node (ref "Clock5") (pin "5") (pinfunction "5_5") (pintype "passive"))
      (node (ref "U5") (pin "14") (pinfunction "5_14") (pintype "output"))
    )
    (net (code "98") (name "Net-(U5-6)") (class "Default")
      (node (ref "Clock5") (pin "3") (pinfunction "3_3") (pintype "passive"))
      (node (ref "U5") (pin "11") (pinfunction "6_11") (pintype "output"))
    )
    (net (code "99") (name "Net-(U5-7)") (class "Default")
      (node (ref "Clock5") (pin "2") (pinfunction "2_2") (pintype "passive"))
      (node (ref "U5") (pin "10") (pinfunction "7_10") (pintype "output"))
    )
    (net (code "100") (name "Net-(U5-8)") (class "Default")
      (node (ref "Clock5") (pin "10") (pinfunction "10_10") (pintype "passive"))
      (node (ref "U5") (pin "1") (pinfunction "8_1") (pintype "output"))
    )
    (net (code "101") (name "Net-(U5-9)") (class "Default")
      (node (ref "Clock5") (pin "9") (pinfunction "9_9") (pintype "passive"))
      (node (ref "U5") (pin "2") (pinfunction "9_2") (pintype "output"))
    )
    (net (code "102") (name "Net-(U6-0)") (class "Default")
      (node (ref "Clock6") (pin "7") (pinfunction "7_7") (pintype "passive"))
      (node (ref "U6") (pin "16") (pinfunction "0_16") (pintype "output"))
    )
    (net (code "103") (name "Net-(U6-1)") (class "Default")
      (node (ref "Clock6") (pin "6") (pinfunction "6_6") (pintype "passive"))
      (node (ref "U6") (pin "15") (pinfunction "1_15") (pintype "output"))
    )
    (net (code "104") (name "Net-(U6-2)") (class "Default")
      (node (ref "Clock6") (pin "8") (pinfunction "8_8") (pintype "passive"))
      (node (ref "U6") (pin "8") (pinfunction "2_8") (pintype "output"))
    )
    (net (code "105") (name "Net-(U6-3)") (class "Default")
      (node (ref "Clock6") (pin "1") (pinfunction "1_1") (pintype "passive"))
      (node (ref "U6") (pin "9") (pinfunction "3_9") (pintype "output"))
    )
    (net (code "106") (name "Net-(U6-4)") (class "Default")
      (node (ref "Clock6") (pin "4") (pinfunction "4_4") (pintype "passive"))
      (node (ref "U6") (pin "13") (pinfunction "4_13") (pintype "output"))
    )
    (net (code "107") (name "Net-(U6-5)") (class "Default")
      (node (ref "Clock6") (pin "5") (pinfunction "5_5") (pintype "passive"))
      (node (ref "U6") (pin "14") (pinfunction "5_14") (pintype "output"))
    )
    (net (code "108") (name "Net-(U6-6)") (class "Default")
      (node (ref "Clock6") (pin "3") (pinfunction "3_3") (pintype "passive"))
      (node (ref "U6") (pin "11") (pinfunction "6_11") (pintype "output"))
    )
    (net (code "109") (name "Net-(U6-7)") (class "Default")
      (node (ref "Clock6") (pin "2") (pinfunction "2_2") (pintype "passive"))
      (node (ref "U6") (pin "10") (pinfunction "7_10") (pintype "output"))
    )
    (net (code "110") (name "Net-(U6-8)") (class "Default")
      (node (ref "Clock6") (pin "10") (pinfunction "10_10") (pintype "passive"))
      (node (ref "U6") (pin "1") (pinfunction "8_1") (pintype "output"))
    )
    (net (code "111") (name "Net-(U6-9)") (class "Default")
      (node (ref "Clock6") (pin "9") (pinfunction "9_9") (pintype "passive"))
      (node (ref "U6") (pin "2") (pinfunction "9_2") (pintype "output"))
    )
    (net (code "112") (name "Net-(U7-IN)") (class "Default")
      (node (ref "C8") (pin "2") (pinfunction "2_2") (pintype "passive"))
      (node (ref "J1") (pin "2") (pinfunction "2_2") (pintype "passive"))
      (node (ref "U7") (pin "3") (pinfunction "IN_3") (pintype "input"))
    )
    (net (code "113") (name "unconnected-(IC3-QH'-Pad9)") (class "Default")
      (node (ref "IC3") (pin "9") (pinfunction "QH'_9") (pintype "passive"))
    )
    (net (code "114") (name "unconnected-(MCU1A-3V3-PadJ1_11)") (class "Default")
      (node (ref "MCU1") (pin "J1_11") (pinfunction "3V3_J1_11") (pintype "power_in"))
    )
    (net (code "115") (name "unconnected-(MCU1A-A0-PadJ1_1)") (class "Default")
      (node (ref "MCU1") (pin "J1_1") (pinfunction "A0_J1_1") (pintype "bidirectional"))
    )
    (net (code "116") (name "unconnected-(MCU1A-CLK-PadJ1_9)") (class "Default")
      (node (ref "MCU1") (pin "J1_9") (pinfunction "CLK_J1_9") (pintype "bidirectional"))
    )
    (net (code "117") (name "unconnected-(MCU1A-CMD-PadJ1_7)") (class "Default")
      (node (ref "MCU1") (pin "J1_7") (pinfunction "CMD_J1_7") (pintype "bidirectional"))
    )
    (net (code "118") (name "unconnected-(MCU1A-EN-PadJ1_12)") (class "Default")
      (node (ref "MCU1") (pin "J1_12") (pinfunction "EN_J1_12") (pintype "input+no_connect"))
    )
    (net (code "119") (name "unconnected-(MCU1A-RST-PadJ1_13)") (class "Default")
      (node (ref "MCU1") (pin "J1_13") (pinfunction "RST_J1_13") (pintype "input+no_connect"))
    )
    (net (code "120") (name "unconnected-(MCU1A-RSV1-PadJ1_2)") (class "Default")
      (node (ref "MCU1") (pin "J1_2") (pinfunction "RSV1_J1_2") (pintype "bidirectional"))
    )
    (net (code "121") (name "unconnected-(MCU1A-RSV2-PadJ1_3)") (class "Default")
      (node (ref "MCU1") (pin "J1_3") (pinfunction "RSV2_J1_3") (pintype "bidirectional"))
    )
    (net (code "122") (name "unconnected-(MCU1A-SD0-PadJ1_8)") (class "Default")
      (node (ref "MCU1") (pin "J1_8") (pinfunction "SD0_J1_8") (pintype "bidirectional"))
    )
    (net (code "123") (name "unconnected-(MCU1A-SD1-PadJ1_6)") (class "Default")
      (node (ref "MCU1") (pin "J1_6") (pinfunction "SD1_J1_6") (pintype "bidirectional"))
    )
    (net (code "124") (name "unconnected-(MCU1A-SD2-PadJ1_5)") (class "Default")
      (node (ref "MCU1") (pin "J1_5") (pinfunction "SD2_J1_5") (pintype "bidirectional"))
    )
    (net (code "125") (name "unconnected-(MCU1A-SD3-PadJ1_4)") (class "Default")
      (node (ref "MCU1") (pin "J1_4") (pinfunction "SD3_J1_4") (pintype "bidirectional"))
    )
    (net (code "126") (name "unconnected-(MCU1B-3V3-PadJ2_6)") (class "Default")
      (node (ref "MCU1") (pin "J2_6") (pinfunction "3V3_J2_6") (pintype "power_in"))
    )
    (net (code "127") (name "unconnected-(MCU1B-3V3-PadJ2_15)") (class "Default")
      (node (ref "MCU1") (pin "J2_15") (pinfunction "3V3_J2_15") (pintype "power_in"))
    )
    (net (code "128") (name "unconnected-(MCU1B-D0-PadJ2_1)") (class "Default")
      (node (ref "MCU1") (pin "J2_1") (pinfunction "D0_J2_1") (pintype "bidirectional"))
    )
    (net (code "129") (name "unconnected-(MCU1B-D4-PadJ2_5)") (class "Default")
      (node (ref "MCU1") (pin "J2_5") (pinfunction "D4_J2_5") (pintype "bidirectional"))
    )
    (net (code "130") (name "unconnected-(MCU1B-D9-PadJ2_12)") (class "Default")
      (node (ref "MCU1") (pin "J2_12") (pinfunction "D9_J2_12") (pintype "bidirectional"))
    )
    (net (code "131") (name "unconnected-(MCU1B-D10-PadJ2_13)") (class "Default")
      (node (ref "MCU1") (pin "J2_13") (pinfunction "D10_J2_13") (pintype "bidirectional"))
    )
  )
)
